# Rev_1_0.net
KiCad netlist of a schematic drawn in Altium Designer
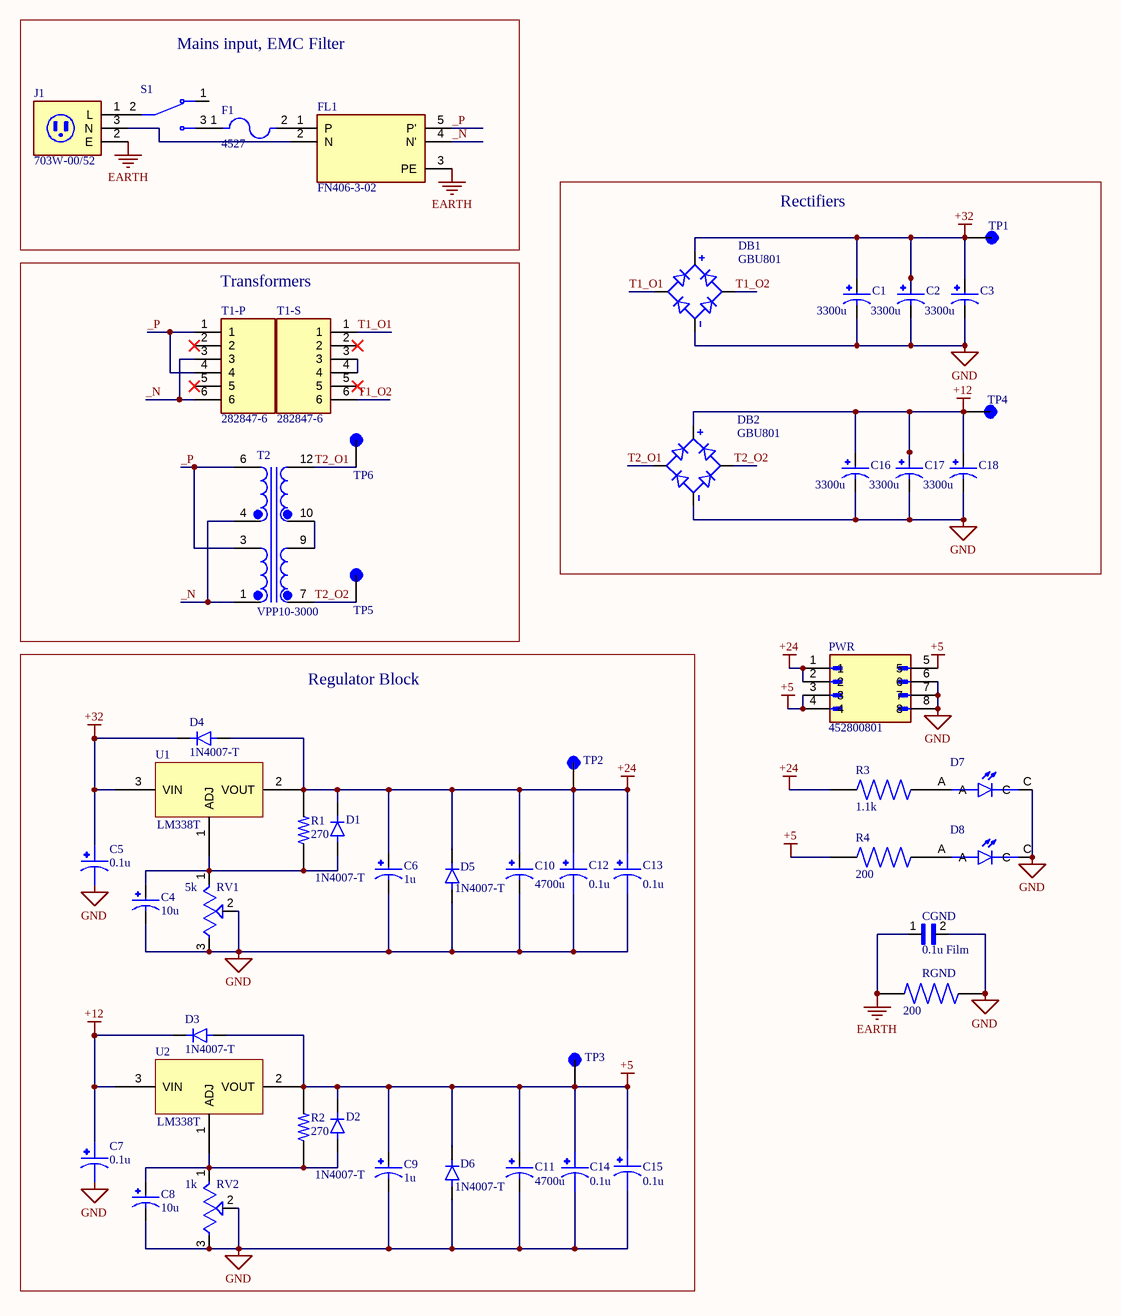
[diagram p0: Rev 1.0.SchDoc]

(export (version "E")
  (design (tool "Eeschema 10.0.6"))
  (components
    (comp (ref "C1")
      (value "UVZ1H332MHD")
      (footprint "CAPPRD750W80D1800H3550")
      (description "NHG-A")
      (fields (field (name "MP") "ECA1VHG472") (field (name "MF") "{'manufacturer': u'Panasonic'}"))
      (libsource (lib "Stepper_PSU") (part "ECA1VHG472"))
    )
    (comp (ref "C2")
      (value "UVZ1H332MHD")
      (footprint "CAPPRD750W80D1800H3550")
      (description "NHG-A")
      (fields (field (name "MP") "ECA1VHG472") (field (name "MF") "{'manufacturer': u'Panasonic'}"))
      (libsource (lib "Stepper_PSU") (part "ECA1VHG472"))
    )
    (comp (ref "C3")
      (value "UVZ1H332MHD")
      (footprint "CAPPRD750W80D1800H3550")
      (description "NHG-A")
      (fields (field (name "MP") "ECA1VHG472") (field (name "MF") "{'manufacturer': u'Panasonic'}"))
      (libsource (lib "Stepper_PSU") (part "ECA1VHG472"))
    )
    (comp (ref "C4")
      (value "10u")
      (footprint "6.35mm Tantalum Radial")
      (description "NHG-A")
      (fields (field (name "MP") "ECA1VHG472") (field (name "MF") "{'manufacturer': u'Panasonic'}"))
      (libsource (lib "Stepper_PSU") (part "ECA1VHG472"))
    )
    (comp (ref "C5")
      (value "0.1u")
      (footprint "CAPPRD200W50D550H1250")
      (description "0.47ÂµF 100V Aluminum Electrolytic Capacitors Radial, Can 2000 Hrs @ 85Â°C")
      (fields (field (name "MP") "UVR1H0R1MDD") (field (name "MF") "{'manufacturer': u'Nichicon'}"))
      (libsource (lib "Stepper_PSU") (part "UVR1H0R1MDD"))
    )
    (comp (ref "C6")
      (value "1u")
      (footprint "6.35mm Tantalum Radial")
      (description "NHG-A")
      (fields (field (name "MP") "ECA1VHG472") (field (name "MF") "{'manufacturer': u'Panasonic'}"))
      (libsource (lib "Stepper_PSU") (part "ECA1VHG472"))
    )
    (comp (ref "C7")
      (value "0.1u")
      (footprint "CAPPRD200W50D550H1250")
      (description "0.47ÂµF 100V Aluminum Electrolytic Capacitors Radial, Can 2000 Hrs @ 85Â°C")
      (fields (field (name "MP") "UVR1H0R1MDD") (field (name "MF") "{'manufacturer': u'Nichicon'}"))
      (libsource (lib "Stepper_PSU") (part "UVR1H0R1MDD"))
    )
    (comp (ref "C8")
      (value "10u")
      (footprint "6.35mm Tantalum Radial")
      (description "NHG-A")
      (fields (field (name "MP") "ECA1VHG472") (field (name "MF") "{'manufacturer': u'Panasonic'}"))
      (libsource (lib "Stepper_PSU") (part "ECA1VHG472"))
    )
    (comp (ref "C9")
      (value "1u")
      (footprint "6.35mm Tantalum Radial")
      (description "NHG-A")
      (fields (field (name "MP") "ECA1VHG472") (field (name "MF") "{'manufacturer': u'Panasonic'}"))
      (libsource (lib "Stepper_PSU") (part "ECA1VHG472"))
    )
    (comp (ref "C10")
      (value "4700u")
      (footprint "CAPPRD750W80D1800H3550")
      (description "NHG-A")
      (fields (field (name "MP") "ECA1VHG472") (field (name "MF") "{'manufacturer': u'Panasonic'}"))
      (libsource (lib "Stepper_PSU") (part "ECA1VHG472"))
    )
    (comp (ref "C11")
      (value "4700u")
      (footprint "CAPPRD750W80D1800H3550")
      (description "NHG-A")
      (fields (field (name "MP") "ECA1VHG472") (field (name "MF") "{'manufacturer': u'Panasonic'}"))
      (libsource (lib "Stepper_PSU") (part "ECA1VHG472"))
    )
    (comp (ref "C12")
      (value "0.1u")
      (footprint "CAPPRD200W50D550H1250")
      (description "0.47ÂµF 100V Aluminum Electrolytic Capacitors Radial, Can 2000 Hrs @ 85Â°C")
      (fields (field (name "MP") "UVR1H0R1MDD") (field (name "MF") "{'manufacturer': u'Nichicon'}"))
      (libsource (lib "Stepper_PSU") (part "UVR1H0R1MDD"))
    )
    (comp (ref "C13")
      (value "0.1u")
      (footprint "CAPPRD200W50D550H1250")
      (description "0.47ÂµF 100V Aluminum Electrolytic Capacitors Radial, Can 2000 Hrs @ 85Â°C")
      (fields (field (name "MP") "UVR1H0R1MDD") (field (name "MF") "{'manufacturer': u'Nichicon'}"))
      (libsource (lib "Stepper_PSU") (part "UVR1H0R1MDD"))
    )
    (comp (ref "C14")
      (value "0.1u")
      (footprint "CAPPRD200W50D550H1250")
      (description "0.47ÂµF 100V Aluminum Electrolytic Capacitors Radial, Can 2000 Hrs @ 85Â°C")
      (fields (field (name "MP") "UVR1H0R1MDD") (field (name "MF") "{'manufacturer': u'Nichicon'}"))
      (libsource (lib "Stepper_PSU") (part "UVR1H0R1MDD"))
    )
    (comp (ref "C15")
      (value "0.1u")
      (footprint "CAPPRD200W50D550H1250")
      (description "0.47ÂµF 100V Aluminum Electrolytic Capacitors Radial, Can 2000 Hrs @ 85Â°C")
      (fields (field (name "MP") "UVR1H0R1MDD") (field (name "MF") "{'manufacturer': u'Nichicon'}"))
      (libsource (lib "Stepper_PSU") (part "UVR1H0R1MDD"))
    )
    (comp (ref "C16")
      (value "UVZ1H332MHD")
      (footprint "CAPPRD750W80D1800H3550")
      (description "NHG-A")
      (fields (field (name "MP") "ECA1VHG472") (field (name "MF") "{'manufacturer': u'Panasonic'}"))
      (libsource (lib "Stepper_PSU") (part "ECA1VHG472"))
    )
    (comp (ref "C17")
      (value "UVZ1H332MHD")
      (footprint "CAPPRD750W80D1800H3550")
      (description "NHG-A")
      (fields (field (name "MP") "ECA1VHG472") (field (name "MF") "{'manufacturer': u'Panasonic'}"))
      (libsource (lib "Stepper_PSU") (part "ECA1VHG472"))
    )
    (comp (ref "C18")
      (value "UVZ1H332MHD")
      (footprint "CAPPRD750W80D1800H3550")
      (description "NHG-A")
      (fields (field (name "MP") "ECA1VHG472") (field (name "MF") "{'manufacturer': u'Panasonic'}"))
      (libsource (lib "Stepper_PSU") (part "ECA1VHG472"))
    )
    (comp (ref "CGND")
      (value "0.1u Film")
      (footprint "CAPRR500W50L730T450H950")
      (fields (field (name "MP") "B32529C3104K289") (field (name "MF") "{'manufacturer': u'EPCOS'}"))
      (libsource (lib "Stepper_PSU") (part "B32529C3104K289"))
    )
    (comp (ref "D1")
      (value "1N4007-T")
      (footprint "DIOAD780W78L463D236")
      (fields (field (name "MF") "{'manufacturer': u'Diodes Incorporated'}"))
      (libsource (lib "Stepper_PSU") (part "1N4007-T"))
    )
    (comp (ref "D2")
      (value "1N4007-T")
      (footprint "DIOAD780W78L463D236")
      (fields (field (name "MF") "{'manufacturer': u'Diodes Incorporated'}"))
      (libsource (lib "Stepper_PSU") (part "1N4007-T"))
    )
    (comp (ref "D3")
      (value "1N4007-T")
      (footprint "DIOAD780W78L463D236")
      (fields (field (name "MF") "{'manufacturer': u'Diodes Incorporated'}"))
      (libsource (lib "Stepper_PSU") (part "1N4007-T"))
    )
    (comp (ref "D4")
      (value "1N4007-T")
      (footprint "DIOAD780W78L463D236")
      (fields (field (name "MF") "{'manufacturer': u'Diodes Incorporated'}"))
      (libsource (lib "Stepper_PSU") (part "1N4007-T"))
    )
    (comp (ref "D5")
      (value "1N4007-T")
      (footprint "DIOAD780W78L463D236")
      (fields (field (name "MF") "{'manufacturer': u'Diodes Incorporated'}"))
      (libsource (lib "Stepper_PSU") (part "1N4007-T"))
    )
    (comp (ref "D6")
      (value "1N4007-T")
      (footprint "DIOAD780W78L463D236")
      (fields (field (name "MF") "{'manufacturer': u'Diodes Incorporated'}"))
      (libsource (lib "Stepper_PSU") (part "1N4007-T"))
    )
    (comp (ref "D7")
      (value "WP7113ID")
      (footprint "WP7113ID:LED_WP7113ID")
      (description "LED; Thru-Hole; Green; T1-3/4; 5mm; Clear Lens; 25ma; 565nm; 200mcd; Round")
      (fields (field (name "MF") "{'manufacturer': u'Kingbright'}"))
      (libsource (lib "*") (part "WP7113ID"))
    )
    (comp (ref "D8")
      (value "WP7113ID")
      (footprint "WP7113ID:LED_WP7113ID")
      (description "LED; Thru-Hole; Green; T1-3/4; 5mm; Clear Lens; 25ma; 565nm; 200mcd; Round")
      (fields (field (name "MF") "{'manufacturer': u'Kingbright'}"))
      (libsource (lib "*") (part "WP7113ID"))
    )
    (comp (ref "DB1")
      (value "GBU801")
      (footprint "SIP343W114P508L2205H2134Q4")
      (fields (field (name "MF") "{'manufacturer': u'Diodes Inc.'}"))
      (libsource (lib "Stepper_PSU") (part "GBU801"))
    )
    (comp (ref "DB2")
      (value "GBU801")
      (footprint "SIP343W114P508L2205H2134Q4")
      (fields (field (name "MF") "{'manufacturer': u'Diodes Inc.'}"))
      (libsource (lib "Stepper_PSU") (part "GBU801"))
    )
    (comp (ref "F1")
      (value "4527")
      (footprint "FUSE_4527")
      (fields (field (name "MF") "{'manufacturer': u'Keystone'}"))
      (libsource (lib "Stepper_PSU") (part "4527"))
    )
    (comp (ref "FL1")
      (value "FN406-3-02")
      (footprint "FIL_FN406-3-02")
      (description "Single Phase EMC/EMI Line Filter 3A 250VAC DC ~ 400Hz Single Stage PC Pins")
      (fields (field (name "MF") "{'manufacturer': u'Schaffner EMC'}"))
      (libsource (lib "Stepper_PSU") (part "FN406-3-02"))
    )
    (comp (ref "J1")
      (value "703W-00/52")
      (footprint "703W-00_52:QUALTEK_703W-00/52")
      (description "3 Position 250 V 10 A Male Pins AC Receptacle Right Angle Connector")
      (fields (field (name "MF") "{'manufacturer': u'Qualtek'}"))
      (libsource (lib "*") (part "703W-00/52"))
    )
    (comp (ref "PWR")
      (value "452800801")
      (footprint "MOLEX_452800801")
      (fields (field (name "MF") "{'manufacturer': u'Molex'}"))
      (libsource (lib "Stepper_Controller") (part "452800801"))
    )
    (comp (ref "R1")
      (value "270")
      (footprint "RESAD730W45L360D200")
      (description "Res Carbon Film 680 Ohm 5% 0.125W(1/8W) -400ppm/C to 0ppm/C Conformal Coated AXL T/R")
      (fields
        (field (name "MP") "CF18JT680R")
        (field (name "MF") "{'manufacturer': u'Stackpole Electronics'}")
      )
      (libsource (lib "Stepper_PSU") (part "CF18JT680R"))
    )
    (comp (ref "R2")
      (value "270")
      (footprint "RESAD730W45L360D200")
      (description "Res Carbon Film 680 Ohm 5% 0.125W(1/8W) -400ppm/C to 0ppm/C Conformal Coated AXL T/R")
      (fields
        (field (name "MP") "CF18JT680R")
        (field (name "MF") "{'manufacturer': u'Stackpole Electronics'}")
      )
      (libsource (lib "Stepper_PSU") (part "CF18JT680R"))
    )
    (comp (ref "R3")
      (value "1.1k")
      (footprint "RESAD1520W70L1030D380")
      (description "5.1 Ohms +/-5% 0.5W, 1/2W Through Hole Resistor Axial Pulse Withstanding Carbon Composition")
      (fields
        (field (name "MF") "{'manufacturer': u'TE Connectivity / AMP'}")
        (field (name "MP") "CBT50J5R1")
      )
      (libsource (lib "Stepper_PSU") (part "CBT50J5R1"))
    )
    (comp (ref "R4")
      (value "200")
      (footprint "RESAD1520W70L1030D380")
      (description "5.1 Ohms +/-5% 0.5W, 1/2W Through Hole Resistor Axial Pulse Withstanding Carbon Composition")
      (fields
        (field (name "MF") "{'manufacturer': u'TE Connectivity / AMP'}")
        (field (name "MP") "CBT50J5R1")
      )
      (libsource (lib "Stepper_PSU") (part "CBT50J5R1"))
    )
    (comp (ref "RGND")
      (value "200")
      (footprint "RESAD1520W70L1030D380")
      (description "5.1 Ohms +/-5% 0.5W, 1/2W Through Hole Resistor Axial Pulse Withstanding Carbon Composition")
      (fields
        (field (name "MF") "{'manufacturer': u'TE Connectivity / AMP'}")
        (field (name "MP") "CBT50J5R1")
      )
      (libsource (lib "Stepper_PSU") (part "CBT50J5R1"))
    )
    (comp (ref "RV1")
      (value "5k")
      (footprint "TRIM_3306F-1-502")
      (description "2 kOhms 0.2W, 1/5W PC Pins Through Hole Trimmer Potentiometer Cermet 1 Turn Top Adjustment")
      (fields (field (name "MP") "3306F-1-502") (field (name "MF") "{'manufacturer': u'Bourns'}"))
      (libsource (lib "Stepper_PSU") (part "3306F-1-502"))
    )
    (comp (ref "RV2")
      (value "1k")
      (footprint "TRIM_3306F-1-502")
      (description "2 kOhms 0.2W, 1/5W PC Pins Through Hole Trimmer Potentiometer Cermet 1 Turn Top Adjustment")
      (fields (field (name "MP") "3306F-1-502") (field (name "MF") "{'manufacturer': u'Bourns'}"))
      (libsource (lib "Stepper_PSU") (part "3306F-1-502"))
    )
    (comp (ref "S1")
      (value "300SP1J1BLKM7QE")
      (footprint "SW_300SP1J1BLKM7QE")
      (fields (field (name "MF") "{'manufacturer': u'E-Switch'}"))
      (libsource (lib "Stepper_PSU") (part "300SP1J1BLKM7QE"))
    )
    (comp (ref "T1-P")
      (value "282847-6")
      (footprint "TE_282847-6")
      (fields (field (name "MF") "{'manufacturer': u'TE Connectivity'}"))
      (libsource (lib "") (part "282847-6_1"))
    )
    (comp (ref "T1-S")
      (value "282847-6")
      (footprint "TE_282847-6")
      (fields (field (name "MF") "{'manufacturer': u'TE Connectivity'}"))
      (libsource (lib "Stepper_PSU") (part "282847-6"))
    )
    (comp (ref "T2")
      (value "VPP10-3000")
      (footprint "XFMR_VPP10-3000")
      (description "Power Transformer 4000Vrms Dual Prim. Dual Sec. 230V/115V Prim. 10V/5V Sec. Through Hole")
      (fields (field (name "MF") "{'manufacturer': u'Triad Magnetics'}"))
      (libsource (lib "Stepper_PSU") (part "VPP10-3000"))
    )
    (comp (ref "TP1")
      (value "5000")
      (footprint "KEYSTONE_5000")
      (fields (field (name "MF") "{'manufacturer': u'Keystone Electronics'}"))
      (libsource (lib "Stepper_PSU") (part "5000"))
    )
    (comp (ref "TP2")
      (value "5000")
      (footprint "KEYSTONE_5000")
      (fields (field (name "MF") "{'manufacturer': u'Keystone Electronics'}"))
      (libsource (lib "Stepper_PSU") (part "5000"))
    )
    (comp (ref "TP3")
      (value "5000")
      (footprint "KEYSTONE_5000")
      (fields (field (name "MF") "{'manufacturer': u'Keystone Electronics'}"))
      (libsource (lib "Stepper_PSU") (part "5000"))
    )
    (comp (ref "TP4")
      (value "5000")
      (footprint "KEYSTONE_5000")
      (fields (field (name "MF") "{'manufacturer': u'Keystone Electronics'}"))
      (libsource (lib "Stepper_PSU") (part "5000"))
    )
    (comp (ref "TP5")
      (value "5000")
      (footprint "KEYSTONE_5000")
      (fields (field (name "MF") "{'manufacturer': u'Keystone Electronics'}"))
      (libsource (lib "Stepper_PSU") (part "5000"))
    )
    (comp (ref "TP6")
      (value "5000")
      (footprint "KEYSTONE_5000")
      (fields (field (name "MF") "{'manufacturer': u'Keystone Electronics'}"))
      (libsource (lib "Stepper_PSU") (part "5000"))
    )
    (comp (ref "U1")
      (value "LM338T")
      (footprint "TO254P1054X470X1955-3")
      (libsource (lib "PSULib") (part "LM338T/NOPB-ND"))
    )
    (comp (ref "U2")
      (value "LM338T")
      (footprint "TO254P1054X470X1955-3")
      (libsource (lib "PSULib") (part "LM338T/NOPB-ND"))
    )
  )
  (nets
    (net (code "1") (name "+5") (class "Default")
      (node (ref "C11") (pin "P") (pinfunction "P_P") (pintype "passive"))
      (node (ref "C14") (pin "1") (pinfunction "1_1") (pintype "passive"))
      (node (ref "C15") (pin "1") (pinfunction "1_1") (pintype "passive"))
      (node (ref "C9") (pin "P") (pinfunction "P_P") (pintype "passive"))
      (node (ref "D2") (pin "K") (pinfunction "K_K") (pintype "passive"))
      (node (ref "D3") (pin "A") (pinfunction "A_A") (pintype "passive"))
      (node (ref "D6") (pin "K") (pinfunction "K_K") (pintype "passive"))
      (node (ref "PWR") (pin "3") (pinfunction "3_3") (pintype "passive"))
      (node (ref "PWR") (pin "4") (pinfunction "4_4") (pintype "passive"))
      (node (ref "PWR") (pin "5") (pinfunction "5_5") (pintype "passive"))
      (node (ref "R2") (pin "2") (pinfunction "2_2") (pintype "passive"))
      (node (ref "R4") (pin "1") (pinfunction "1_1") (pintype "passive"))
      (node (ref "TP3") (pin "TP") (pinfunction "TP_TP") (pintype "passive"))
      (node (ref "U2") (pin "2") (pinfunction "VOUT_2") (pintype "passive"))
    )
    (net (code "2") (name "+12") (class "Default")
      (node (ref "C16") (pin "P") (pinfunction "P_P") (pintype "passive"))
      (node (ref "C17") (pin "P") (pinfunction "P_P") (pintype "passive"))
      (node (ref "C18") (pin "P") (pinfunction "P_P") (pintype "passive"))
      (node (ref "C7") (pin "1") (pinfunction "1_1") (pintype "passive"))
      (node (ref "D3") (pin "K") (pinfunction "K_K") (pintype "passive"))
      (node (ref "DB2") (pin "POS") (pinfunction "POS_POS") (pintype "passive"))
      (node (ref "TP4") (pin "TP") (pinfunction "TP_TP") (pintype "passive"))
      (node (ref "U2") (pin "3") (pinfunction "VIN_3") (pintype "passive"))
    )
    (net (code "3") (name "+24") (class "Default")
      (node (ref "C10") (pin "P") (pinfunction "P_P") (pintype "passive"))
      (node (ref "C12") (pin "1") (pinfunction "1_1") (pintype "passive"))
      (node (ref "C13") (pin "1") (pinfunction "1_1") (pintype "passive"))
      (node (ref "C6") (pin "P") (pinfunction "P_P") (pintype "passive"))
      (node (ref "D1") (pin "K") (pinfunction "K_K") (pintype "passive"))
      (node (ref "D4") (pin "A") (pinfunction "A_A") (pintype "passive"))
      (node (ref "D5") (pin "K") (pinfunction "K_K") (pintype "passive"))
      (node (ref "PWR") (pin "1") (pinfunction "1_1") (pintype "passive"))
      (node (ref "PWR") (pin "2") (pinfunction "2_2") (pintype "passive"))
      (node (ref "R1") (pin "2") (pinfunction "2_2") (pintype "passive"))
      (node (ref "R3") (pin "1") (pinfunction "1_1") (pintype "passive"))
      (node (ref "TP2") (pin "TP") (pinfunction "TP_TP") (pintype "passive"))
      (node (ref "U1") (pin "2") (pinfunction "VOUT_2") (pintype "passive"))
    )
    (net (code "4") (name "+32") (class "Default")
      (node (ref "C1") (pin "P") (pinfunction "P_P") (pintype "passive"))
      (node (ref "C2") (pin "P") (pinfunction "P_P") (pintype "passive"))
      (node (ref "C3") (pin "P") (pinfunction "P_P") (pintype "passive"))
      (node (ref "C5") (pin "1") (pinfunction "1_1") (pintype "passive"))
      (node (ref "D4") (pin "K") (pinfunction "K_K") (pintype "passive"))
      (node (ref "DB1") (pin "POS") (pinfunction "POS_POS") (pintype "passive"))
      (node (ref "TP1") (pin "TP") (pinfunction "TP_TP") (pintype "passive"))
      (node (ref "U1") (pin "3") (pinfunction "VIN_3") (pintype "passive"))
    )
    (net (code "5") (name "/T1_O1") (class "Default")
      (node (ref "DB1") (pin "AC2") (pinfunction "AC2_AC2") (pintype "passive"))
      (node (ref "T1-S") (pin "1") (pinfunction "1_1") (pintype "passive"))
    )
    (net (code "6") (name "/T1_O2") (class "Default")
      (node (ref "DB1") (pin "AC1") (pinfunction "AC1_AC1") (pintype "passive"))
      (node (ref "T1-S") (pin "6") (pinfunction "6_6") (pintype "passive"))
    )
    (net (code "7") (name "/T2_O1") (class "Default")
      (node (ref "DB2") (pin "AC2") (pinfunction "AC2_AC2") (pintype "passive"))
      (node (ref "T2") (pin "12") (pinfunction "12_12") (pintype "passive"))
      (node (ref "TP6") (pin "TP") (pinfunction "TP_TP") (pintype "passive"))
    )
    (net (code "8") (name "/T2_O2") (class "Default")
      (node (ref "DB2") (pin "AC1") (pinfunction "AC1_AC1") (pintype "passive"))
      (node (ref "T2") (pin "7") (pinfunction "7_7") (pintype "passive"))
      (node (ref "TP5") (pin "TP") (pinfunction "TP_TP") (pintype "passive"))
    )
    (net (code "9") (name "/_N") (class "Default")
      (node (ref "FL1") (pin "4") (pinfunction "N'_4") (pintype "passive"))
      (node (ref "T1-P") (pin "3") (pinfunction "3_3") (pintype "passive"))
      (node (ref "T1-P") (pin "6") (pinfunction "6_6") (pintype "passive"))
      (node (ref "T2") (pin "1") (pinfunction "1_1") (pintype "passive"))
      (node (ref "T2") (pin "4") (pinfunction "4_4") (pintype "passive"))
    )
    (net (code "10") (name "/_P") (class "Default")
      (node (ref "FL1") (pin "5") (pinfunction "P'_5") (pintype "passive"))
      (node (ref "T1-P") (pin "1") (pinfunction "1_1") (pintype "passive"))
      (node (ref "T1-P") (pin "4") (pinfunction "4_4") (pintype "passive"))
      (node (ref "T2") (pin "3") (pinfunction "3_3") (pintype "passive"))
      (node (ref "T2") (pin "6") (pinfunction "6_6") (pintype "passive"))
    )
    (net (code "11") (name "EARTH") (class "Default")
      (node (ref "CGND") (pin "1") (pinfunction "1_1") (pintype "passive"))
      (node (ref "FL1") (pin "3") (pinfunction "PE_3") (pintype "power_in"))
      (node (ref "J1") (pin "2") (pinfunction "E_2") (pintype "power_in"))
      (node (ref "RGND") (pin "1") (pinfunction "1_1") (pintype "passive"))
    )
    (net (code "12") (name "GND") (class "Default")
      (node (ref "C1") (pin "N") (pinfunction "N_N") (pintype "passive"))
      (node (ref "C10") (pin "N") (pinfunction "N_N") (pintype "passive"))
      (node (ref "C11") (pin "N") (pinfunction "N_N") (pintype "passive"))
      (node (ref "C12") (pin "2") (pinfunction "2_2") (pintype "passive"))
      (node (ref "C13") (pin "2") (pinfunction "2_2") (pintype "passive"))
      (node (ref "C14") (pin "2") (pinfunction "2_2") (pintype "passive"))
      (node (ref "C15") (pin "2") (pinfunction "2_2") (pintype "passive"))
      (node (ref "C16") (pin "N") (pinfunction "N_N") (pintype "passive"))
      (node (ref "C17") (pin "N") (pinfunction "N_N") (pintype "passive"))
      (node (ref "C18") (pin "N") (pinfunction "N_N") (pintype "passive"))
      (node (ref "C2") (pin "N") (pinfunction "N_N") (pintype "passive"))
      (node (ref "C3") (pin "N") (pinfunction "N_N") (pintype "passive"))
      (node (ref "C4") (pin "N") (pinfunction "N_N") (pintype "passive"))
      (node (ref "C5") (pin "2") (pinfunction "2_2") (pintype "passive"))
      (node (ref "C6") (pin "N") (pinfunction "N_N") (pintype "passive"))
      (node (ref "C7") (pin "2") (pinfunction "2_2") (pintype "passive"))
      (node (ref "C8") (pin "N") (pinfunction "N_N") (pintype "passive"))
      (node (ref "C9") (pin "N") (pinfunction "N_N") (pintype "passive"))
      (node (ref "CGND") (pin "2") (pinfunction "2_2") (pintype "passive"))
      (node (ref "D5") (pin "A") (pinfunction "A_A") (pintype "passive"))
      (node (ref "D6") (pin "A") (pinfunction "A_A") (pintype "passive"))
      (node (ref "D7") (pin "C") (pinfunction "C_C") (pintype "passive"))
      (node (ref "D8") (pin "C") (pinfunction "C_C") (pintype "passive"))
      (node (ref "DB1") (pin "NEG") (pinfunction "NEG_NEG") (pintype "passive"))
      (node (ref "DB2") (pin "NEG") (pinfunction "NEG_NEG") (pintype "passive"))
      (node (ref "PWR") (pin "6") (pinfunction "6_6") (pintype "passive"))
      (node (ref "PWR") (pin "7") (pinfunction "7_7") (pintype "passive"))
      (node (ref "PWR") (pin "8") (pinfunction "8_8") (pintype "passive"))
      (node (ref "RGND") (pin "2") (pinfunction "2_2") (pintype "passive"))
      (node (ref "RV1") (pin "2") (pinfunction "W_2") (pintype "passive"))
      (node (ref "RV1") (pin "3") (pinfunction "CW_3") (pintype "passive"))
      (node (ref "RV2") (pin "2") (pinfunction "W_2") (pintype "passive"))
      (node (ref "RV2") (pin "3") (pinfunction "CW_3") (pintype "passive"))
    )
    (net (code "13") (name "Net-(D7-PadA)") (class "Default")
      (node (ref "D7") (pin "A") (pinfunction "A_A") (pintype "passive"))
      (node (ref "R3") (pin "2") (pinfunction "2_2") (pintype "passive"))
    )
    (net (code "14") (name "Net-(D8-PadA)") (class "Default")
      (node (ref "D8") (pin "A") (pinfunction "A_A") (pintype "passive"))
      (node (ref "R4") (pin "2") (pinfunction "2_2") (pintype "passive"))
    )
    (net (code "15") (name "Net-(F1-Pad1)") (class "Default")
      (node (ref "F1") (pin "1") (pinfunction "1_1") (pintype "passive"))
      (node (ref "S1") (pin "3") (pinfunction "3_3") (pintype "passive"))
    )
    (net (code "16") (name "Net-(FL1-N)") (class "Default")
      (node (ref "FL1") (pin "2") (pinfunction "N_2") (pintype "passive"))
      (node (ref "J1") (pin "3") (pinfunction "N_3") (pintype "power_in"))
    )
    (net (code "17") (name "Net-(FL1-P)") (class "Default")
      (node (ref "F1") (pin "2") (pinfunction "2_2") (pintype "passive"))
      (node (ref "FL1") (pin "1") (pinfunction "P_1") (pintype "passive"))
    )
    (net (code "18") (name "Net-(J1-L)") (class "Default")
      (node (ref "J1") (pin "1") (pinfunction "L_1") (pintype "power_in"))
      (node (ref "S1") (pin "2") (pinfunction "2_2") (pintype "passive"))
    )
    (net (code "19") (name "Net-(RV1-CCW)") (class "Default")
      (node (ref "C4") (pin "P") (pinfunction "P_P") (pintype "passive"))
      (node (ref "D1") (pin "A") (pinfunction "A_A") (pintype "passive"))
      (node (ref "R1") (pin "1") (pinfunction "1_1") (pintype "passive"))
      (node (ref "RV1") (pin "1") (pinfunction "CCW_1") (pintype "passive"))
      (node (ref "U1") (pin "1") (pinfunction "ADJ_1") (pintype "passive"))
    )
    (net (code "20") (name "Net-(RV2-CCW)") (class "Default")
      (node (ref "C8") (pin "P") (pinfunction "P_P") (pintype "passive"))
      (node (ref "D2") (pin "A") (pinfunction "A_A") (pintype "passive"))
      (node (ref "R2") (pin "1") (pinfunction "1_1") (pintype "passive"))
      (node (ref "RV2") (pin "1") (pinfunction "CCW_1") (pintype "passive"))
      (node (ref "U2") (pin "1") (pinfunction "ADJ_1") (pintype "passive"))
    )
    (net (code "21") (name "Net-(T1-S-Pad3)") (class "Default")
      (node (ref "T1-S") (pin "3") (pinfunction "3_3") (pintype "passive"))
      (node (ref "T1-S") (pin "4") (pinfunction "4_4") (pintype "passive"))
    )
    (net (code "22") (name "Net-(T2-Pad10)") (class "Default")
      (node (ref "T2") (pin "10") (pinfunction "10_10") (pintype "passive"))
      (node (ref "T2") (pin "9") (pinfunction "9_9") (pintype "passive"))
    )
    (net (code "23") (name "unconnected-(S1-Pad1)") (class "Default")
      (node (ref "S1") (pin "1") (pinfunction "1_1") (pintype "passive"))
    )
    (net (code "24") (name "unconnected-(T1-P-Pad2)") (class "Default")
      (node (ref "T1-P") (pin "2") (pinfunction "2_2") (pintype "passive+no_connect"))
    )
    (net (code "25") (name "unconnected-(T1-P-Pad5)") (class "Default")
      (node (ref "T1-P") (pin "5") (pinfunction "5_5") (pintype "passive+no_connect"))
    )
    (net (code "26") (name "unconnected-(T1-S-Pad2)") (class "Default")
      (node (ref "T1-S") (pin "2") (pinfunction "2_2") (pintype "passive+no_connect"))
    )
    (net (code "27") (name "unconnected-(T1-S-Pad5)") (class "Default")
      (node (ref "T1-S") (pin "5") (pinfunction "5_5") (pintype "passive+no_connect"))
    )
  )
)
